# Controller.net
KiCad netlist of a schematic drawn in Altium Designer
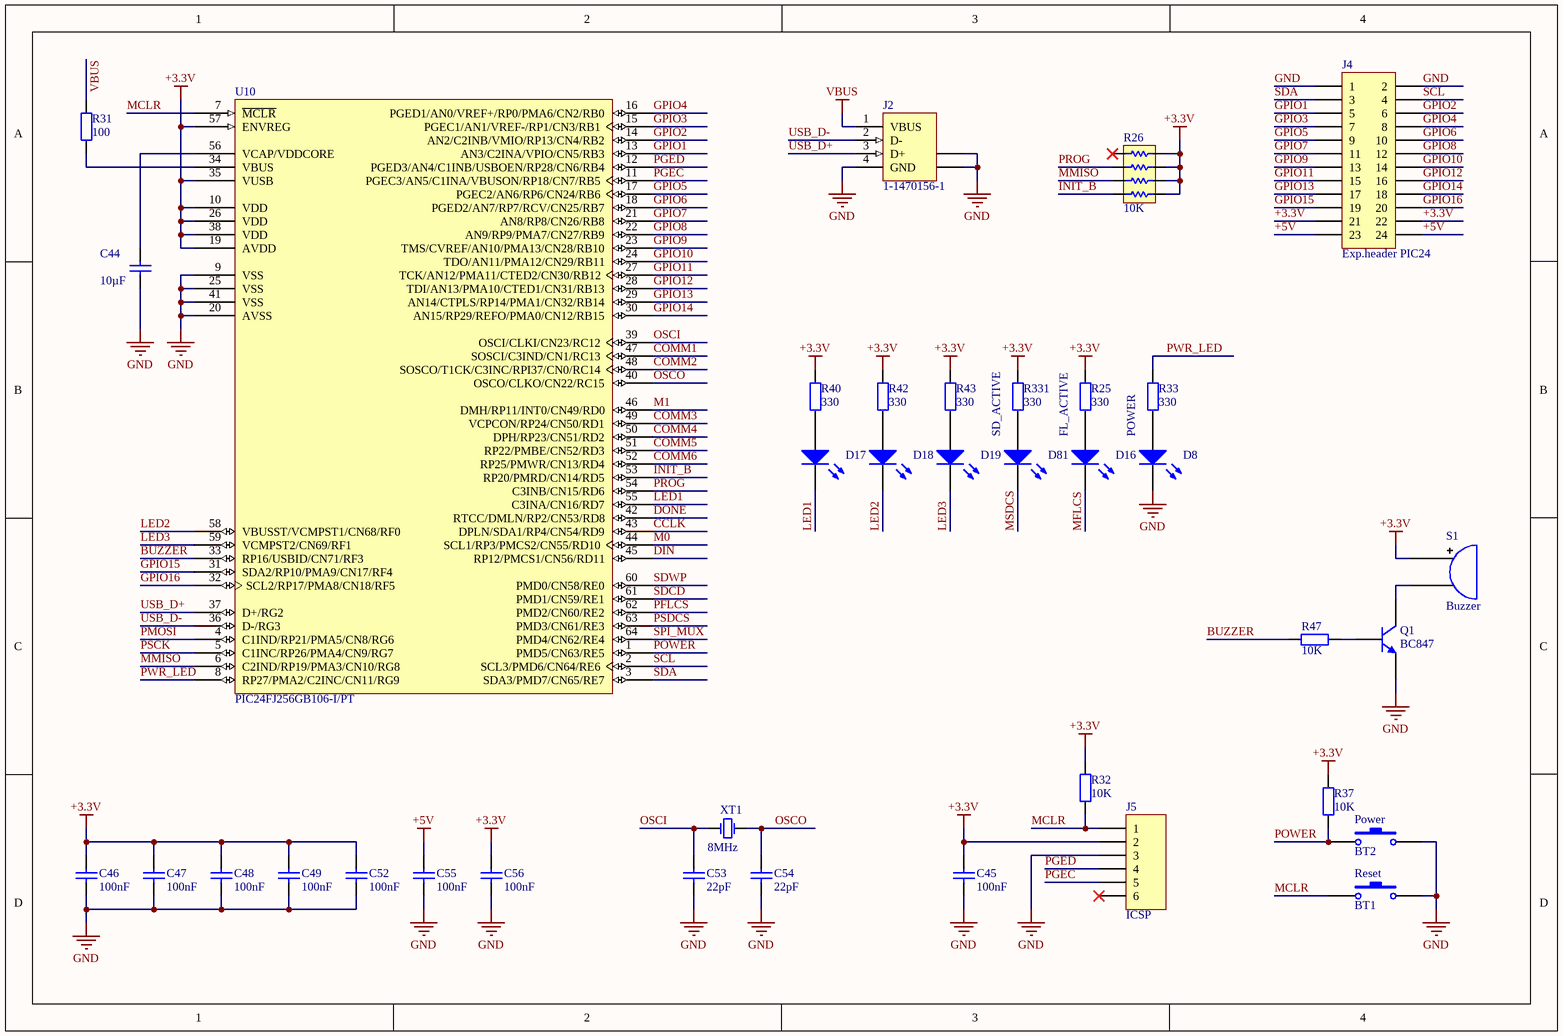
[diagram p0: Controller.SchDoc]

(export (version "E")
  (design (tool "Eeschema 10.0.6"))
  (components
    (comp (ref "C44")
      (value "10µF")
      (footprint "6-0805_n")
      (description "Capacitor")
      (fields (field (name "Comment") "Cap") (field (name "PUBLISHER") "Altium Limited"))
      (libsource (lib "Miscellaneous Devices") (part "Cap"))
    )
    (comp (ref "C45")
      (value "100nF")
      (footprint "6-0805_n")
      (description "Capacitor")
      (fields (field (name "Comment") "Cap") (field (name "PUBLISHER") "Altium Limited"))
      (libsource (lib "Miscellaneous Devices") (part "Cap"))
    )
    (comp (ref "C46")
      (value "100nF")
      (footprint "6-0805_n")
      (description "Capacitor")
      (fields (field (name "Comment") "Cap") (field (name "PUBLISHER") "Altium Limited"))
      (libsource (lib "Miscellaneous Devices") (part "Cap"))
    )
    (comp (ref "C47")
      (value "100nF")
      (footprint "6-0805_n")
      (description "Capacitor")
      (fields (field (name "Comment") "Cap") (field (name "PUBLISHER") "Altium Limited"))
      (libsource (lib "Miscellaneous Devices") (part "Cap"))
    )
    (comp (ref "C48")
      (value "100nF")
      (footprint "6-0805_n")
      (description "Capacitor")
      (fields (field (name "Comment") "Cap") (field (name "PUBLISHER") "Altium Limited"))
      (libsource (lib "Miscellaneous Devices") (part "Cap"))
    )
    (comp (ref "C49")
      (value "100nF")
      (footprint "6-0805_n")
      (description "Capacitor")
      (fields (field (name "Comment") "Cap") (field (name "PUBLISHER") "Altium Limited"))
      (libsource (lib "Miscellaneous Devices") (part "Cap"))
    )
    (comp (ref "C52")
      (value "100nF")
      (footprint "6-0805_n")
      (description "Capacitor")
      (fields (field (name "Comment") "Cap") (field (name "PUBLISHER") "Altium Limited"))
      (libsource (lib "Miscellaneous Devices") (part "Cap"))
    )
    (comp (ref "C53")
      (value "22pF")
      (footprint "6-0805_n")
      (description "Capacitor")
      (fields (field (name "Comment") "Cap") (field (name "PUBLISHER") "Altium Limited"))
      (libsource (lib "Miscellaneous Devices") (part "Cap"))
    )
    (comp (ref "C54")
      (value "22pF")
      (footprint "6-0805_n")
      (description "Capacitor")
      (fields (field (name "Comment") "Cap") (field (name "PUBLISHER") "Altium Limited"))
      (libsource (lib "Miscellaneous Devices") (part "Cap"))
    )
    (comp (ref "C55")
      (value "100nF")
      (footprint "6-0805_n")
      (description "Capacitor")
      (fields (field (name "Comment") "Cap") (field (name "PUBLISHER") "Altium Limited"))
      (libsource (lib "Miscellaneous Devices") (part "Cap"))
    )
    (comp (ref "C56")
      (value "100nF")
      (footprint "6-0805_n")
      (description "Capacitor")
      (fields (field (name "Comment") "Cap") (field (name "PUBLISHER") "Altium Limited"))
      (libsource (lib "Miscellaneous Devices") (part "Cap"))
    )
    (comp (ref "D8")
      (value "POWER")
      (footprint "HDR1X2")
      (description "Typical INFRARED GaAs LED")
      (fields (field (name "PUBLISHER") "Altium Limited"))
      (libsource (lib "Miscellaneous Devices") (part "LED0"))
    )
    (comp (ref "D16")
      (value "FL_ACTIVE")
      (footprint "HDR1X2")
      (description "Typical INFRARED GaAs LED")
      (fields (field (name "PUBLISHER") "Altium Limited"))
      (libsource (lib "Miscellaneous Devices") (part "LED0"))
    )
    (comp (ref "D17")
      (value "SD_ACTIVE")
      (footprint "6-0805_N")
      (description "Typical INFRARED GaAs LED")
      (fields (field (name "PUBLISHER") "Altium Limited"))
      (libsource (lib "Miscellaneous Devices") (part "LED0"))
    )
    (comp (ref "D18")
      (value "SD_ACTIVE")
      (footprint "6-0805_N")
      (description "Typical INFRARED GaAs LED")
      (fields (field (name "PUBLISHER") "Altium Limited"))
      (libsource (lib "Miscellaneous Devices") (part "LED0"))
    )
    (comp (ref "D19")
      (value "SD_ACTIVE")
      (footprint "6-0805_N")
      (description "Typical INFRARED GaAs LED")
      (fields (field (name "PUBLISHER") "Altium Limited"))
      (libsource (lib "Miscellaneous Devices") (part "LED0"))
    )
    (comp (ref "D81")
      (value "SD_ACTIVE")
      (footprint "HDR1X2")
      (description "Typical INFRARED GaAs LED")
      (fields (field (name "PUBLISHER") "Altium Limited"))
      (libsource (lib "Miscellaneous Devices") (part "LED0"))
    )
    (comp (ref "J2")
      (value "1-1470156-1")
      (footprint "440119")
      (description "USB 1.1, Right Angle, Thru-Hole, B Type, Receptacle, 4 Position, White")
      (fields (field (name "PUBLISHER") "Altium Limited"))
      (libsource (lib "AMP Serial Bus USB") (part "1-1470156-1"))
    )
    (comp (ref "J4")
      (value "Exp.header PIC24")
      (footprint "HDR2X12")
      (description "Header, 12-Pin, Dual row")
      (fields (field (name "PUBLISHER") "Altium Limited"))
      (libsource (lib "Miscellaneous Connectors") (part "Header 12X2"))
    )
    (comp (ref "J5")
      (value "ICSP")
      (footprint "HDR1X6")
      (description "Header, 6-Pin")
      (fields (field (name "PUBLISHER") "Altium Limited"))
      (libsource (lib "Miscellaneous Connectors") (part "Header 6"))
    )
    (comp (ref "Power")
      (value "BT2")
      (footprint "Push Button 6mm - Right Angle")
      (libsource (lib "Switches Buttons") (part "Push Button"))
    )
    (comp (ref "Q1")
      (value "BC847")
      (footprint "SOT23_N")
      (description "NPN 1 GHz Wideband Transistor")
      (fields (field (name "PUBLISHER") "Altium Limited"))
      (libsource (lib "Philips Discrete BJT - RF Transistor") (part "BF547"))
    )
    (comp (ref "R25")
      (value "330")
      (footprint "6-0805_N")
      (description "Resistor")
      (fields (field (name "Comment") "Res2") (field (name "PUBLISHER") "Altium Limited"))
      (libsource (lib "Miscellaneous Devices") (part "Res2"))
    )
    (comp (ref "R26")
      (value "10K")
      (footprint "SMD 4 Resisor Network")
      (libsource (lib "eon_lib") (part "SMD 4 Resistor Network"))
    )
    (comp (ref "R31")
      (value "100")
      (footprint "6-0805_N")
      (description "Resistor")
      (fields (field (name "Comment") "Res2") (field (name "PUBLISHER") "Altium Limited"))
      (libsource (lib "") (part "Res2_1"))
    )
    (comp (ref "R32")
      (value "10K")
      (footprint "6-0805_N")
      (description "Resistor")
      (fields (field (name "Comment") "Res2") (field (name "PUBLISHER") "Altium Limited"))
      (libsource (lib "Miscellaneous Devices") (part "Res2"))
    )
    (comp (ref "R33")
      (value "330")
      (footprint "6-0805_N")
      (description "Resistor")
      (fields (field (name "Comment") "Res2") (field (name "PUBLISHER") "Altium Limited"))
      (libsource (lib "Miscellaneous Devices") (part "Res2"))
    )
    (comp (ref "R37")
      (value "10K")
      (footprint "6-0805_N")
      (description "Resistor")
      (fields (field (name "Comment") "Res2") (field (name "PUBLISHER") "Altium Limited"))
      (libsource (lib "Miscellaneous Devices") (part "Res2"))
    )
    (comp (ref "R40")
      (value "330")
      (footprint "6-0805_N")
      (description "Resistor")
      (fields (field (name "Comment") "Res2") (field (name "PUBLISHER") "Altium Limited"))
      (libsource (lib "Miscellaneous Devices") (part "Res2"))
    )
    (comp (ref "R42")
      (value "330")
      (footprint "6-0805_N")
      (description "Resistor")
      (fields (field (name "Comment") "Res2") (field (name "PUBLISHER") "Altium Limited"))
      (libsource (lib "Miscellaneous Devices") (part "Res2"))
    )
    (comp (ref "R43")
      (value "330")
      (footprint "6-0805_N")
      (description "Resistor")
      (fields (field (name "Comment") "Res2") (field (name "PUBLISHER") "Altium Limited"))
      (libsource (lib "Miscellaneous Devices") (part "Res2"))
    )
    (comp (ref "R47")
      (value "10K")
      (footprint "RESC2012N")
      (description "Resistor")
      (fields (field (name "PUBLISHER") "Altium Limited"))
      (libsource (lib "eon_lib") (part "Resistor"))
    )
    (comp (ref "R331")
      (value "330")
      (footprint "6-0805_N")
      (description "Resistor")
      (fields (field (name "Comment") "Res2") (field (name "PUBLISHER") "Altium Limited"))
      (libsource (lib "Miscellaneous Devices") (part "Res2"))
    )
    (comp (ref "Reset")
      (value "BT1")
      (footprint "Push Button 6mm")
      (libsource (lib "Switches Buttons") (part "Push Button"))
    )
    (comp (ref "S1")
      (value "Buzzer")
      (footprint "Buzzer")
      (description "Magnetic Buzzer")
      (libsource (lib "eon_lib") (part "Buzzer CEM-1206S/WT-1201"))
    )
    (comp (ref "U10")
      (value "PIC24FJ256GB106-I/PT")
      (footprint "TQFP-PT64_N")
      (fields (field (name "PUBLISHER") "Altium Limited"))
      (libsource (lib "Microchip Microcontroller 16-Bit PIC24F") (part "PIC24FJ256GB106-I/PT"))
    )
    (comp (ref "XT1")
      (value "8MHz")
      (footprint "Quartz HC-49")
      (fields (field (name "Comment") "XTAL"))
      (libsource (lib "Passiv") (part "XTAL"))
    )
  )
  (nets
    (net (code "1") (name "+3.3V") (class "Default")
      (node (ref "C45") (pin "2") (pinfunction "2_2") (pintype "passive"))
      (node (ref "C46") (pin "1") (pinfunction "1_1") (pintype "passive"))
      (node (ref "C47") (pin "1") (pinfunction "1_1") (pintype "passive"))
      (node (ref "C48") (pin "1") (pinfunction "1_1") (pintype "passive"))
      (node (ref "C49") (pin "1") (pinfunction "1_1") (pintype "passive"))
      (node (ref "C52") (pin "1") (pinfunction "1_1") (pintype "passive"))
      (node (ref "C56") (pin "2") (pinfunction "2_2") (pintype "passive"))
      (node (ref "J4") (pin "21") (pinfunction "21_21") (pintype "passive"))
      (node (ref "J4") (pin "22") (pinfunction "22_22") (pintype "passive"))
      (node (ref "J5") (pin "2") (pinfunction "2_2") (pintype "passive"))
      (node (ref "R25") (pin "2") (pinfunction "2_2") (pintype "passive"))
      (node (ref "R26") (pin "2") (pinfunction "2_2") (pintype "passive"))
      (node (ref "R26") (pin "4") (pinfunction "4_4") (pintype "passive"))
      (node (ref "R26") (pin "6") (pinfunction "6_6") (pintype "passive"))
      (node (ref "R26") (pin "8") (pinfunction "8_8") (pintype "passive"))
      (node (ref "R32") (pin "2") (pinfunction "2_2") (pintype "passive"))
      (node (ref "R331") (pin "2") (pinfunction "2_2") (pintype "passive"))
      (node (ref "R37") (pin "2") (pinfunction "2_2") (pintype "passive"))
      (node (ref "R40") (pin "2") (pinfunction "2_2") (pintype "passive"))
      (node (ref "R42") (pin "2") (pinfunction "2_2") (pintype "passive"))
      (node (ref "R43") (pin "2") (pinfunction "2_2") (pintype "passive"))
      (node (ref "S1") (pin "1") (pinfunction "1_1") (pintype "passive"))
      (node (ref "U10") (pin "10") (pinfunction "VDD_10") (pintype "power_in"))
      (node (ref "U10") (pin "19") (pinfunction "AVDD_19") (pintype "power_in"))
      (node (ref "U10") (pin "26") (pinfunction "VDD_26") (pintype "power_in"))
      (node (ref "U10") (pin "35") (pinfunction "VUSB_35") (pintype "power_in"))
      (node (ref "U10") (pin "38") (pinfunction "VDD_38") (pintype "power_in"))
      (node (ref "U10") (pin "57") (pinfunction "ENVREG_57") (pintype "input"))
    )
    (net (code "2") (name "+5V") (class "Default")
      (node (ref "C55") (pin "2") (pinfunction "2_2") (pintype "passive"))
      (node (ref "J4") (pin "23") (pinfunction "23_23") (pintype "passive"))
      (node (ref "J4") (pin "24") (pinfunction "24_24") (pintype "passive"))
    )
    (net (code "3") (name "/BUZZER") (class "Default")
      (node (ref "R47") (pin "1") (pinfunction "1_1") (pintype "passive"))
      (node (ref "U10") (pin "33") (pinfunction "RP16/USBID/CN71/RF3_33") (pintype "bidirectional"))
    )
    (net (code "4") (name "/CCLK") (class "Default")
      (node (ref "U10") (pin "43") (pinfunction "DPLN/SDA1/RP4/CN54/RD9_43") (pintype "bidirectional"))
    )
    (net (code "5") (name "/COMM1") (class "Default")
      (node (ref "U10") (pin "47") (pinfunction "SOSCI/C3IND/CN1/RC13_47") (pintype "bidirectional"))
    )
    (net (code "6") (name "/COMM2") (class "Default")
      (node (ref "U10") (pin "48") (pinfunction "SOSCO/T1CK/C3INC/RPI37/CN0/RC14_48") (pintype "bidirectional"))
    )
    (net (code "7") (name "/COMM3") (class "Default")
      (node (ref "U10") (pin "49") (pinfunction "VCPCON/RP24/CN50/RD1_49") (pintype "bidirectional"))
    )
    (net (code "8") (name "/COMM4") (class "Default")
      (node (ref "U10") (pin "50") (pinfunction "DPH/RP23/CN51/RD2_50") (pintype "bidirectional"))
    )
    (net (code "9") (name "/COMM5") (class "Default")
      (node (ref "U10") (pin "51") (pinfunction "RP22/PMBE/CN52/RD3_51") (pintype "bidirectional"))
    )
    (net (code "10") (name "/COMM6") (class "Default")
      (node (ref "U10") (pin "52") (pinfunction "RP25/PMWR/CN13/RD4_52") (pintype "bidirectional"))
    )
    (net (code "11") (name "/DIN") (class "Default")
      (node (ref "U10") (pin "45") (pinfunction "RP12/PMCS1/CN56/RD11_45") (pintype "bidirectional"))
    )
    (net (code "12") (name "/DONE") (class "Default")
      (node (ref "U10") (pin "42") (pinfunction "RTCC/DMLN/RP2/CN53/RD8_42") (pintype "bidirectional"))
    )
    (net (code "13") (name "/GPIO1") (class "Default")
      (node (ref "J4") (pin "5") (pinfunction "5_5") (pintype "passive"))
      (node (ref "U10") (pin "13") (pinfunction "AN3/C2INA/VPIO/CN5/RB3_13") (pintype "bidirectional"))
    )
    (net (code "14") (name "/GPIO2") (class "Default")
      (node (ref "J4") (pin "6") (pinfunction "6_6") (pintype "passive"))
      (node (ref "U10") (pin "14") (pinfunction "AN2/C2INB/VMIO/RP13/CN4/RB2_14") (pintype "bidirectional"))
    )
    (net (code "15") (name "/GPIO3") (class "Default")
      (node (ref "J4") (pin "7") (pinfunction "7_7") (pintype "passive"))
      (node (ref "U10") (pin "15") (pinfunction "PGEC1/AN1/VREF-/RP1/CN3/RB1_15") (pintype "bidirectional"))
    )
    (net (code "16") (name "/GPIO4") (class "Default")
      (node (ref "J4") (pin "8") (pinfunction "8_8") (pintype "passive"))
      (node (ref "U10") (pin "16") (pinfunction "PGED1/AN0/VREF+/RP0/PMA6/CN2/RB0_16") (pintype "bidirectional"))
    )
    (net (code "17") (name "/GPIO5") (class "Default")
      (node (ref "J4") (pin "9") (pinfunction "9_9") (pintype "passive"))
      (node (ref "U10") (pin "17") (pinfunction "PGEC2/AN6/RP6/CN24/RB6_17") (pintype "bidirectional"))
    )
    (net (code "18") (name "/GPIO6") (class "Default")
      (node (ref "J4") (pin "10") (pinfunction "10_10") (pintype "passive"))
      (node (ref "U10") (pin "18") (pinfunction "PGED2/AN7/RP7/RCV/CN25/RB7_18") (pintype "bidirectional"))
    )
    (net (code "19") (name "/GPIO7") (class "Default")
      (node (ref "J4") (pin "11") (pinfunction "11_11") (pintype "passive"))
      (node (ref "U10") (pin "21") (pinfunction "AN8/RP8/CN26/RB8_21") (pintype "bidirectional"))
    )
    (net (code "20") (name "/GPIO8") (class "Default")
      (node (ref "J4") (pin "12") (pinfunction "12_12") (pintype "passive"))
      (node (ref "U10") (pin "22") (pinfunction "AN9/RP9/PMA7/CN27/RB9_22") (pintype "bidirectional"))
    )
    (net (code "21") (name "/GPIO9") (class "Default")
      (node (ref "J4") (pin "13") (pinfunction "13_13") (pintype "passive"))
      (node (ref "U10") (pin "23") (pinfunction "TMS/CVREF/AN10/PMA13/CN28/RB10_23") (pintype "bidirectional"))
    )
    (net (code "22") (name "/GPIO10") (class "Default")
      (node (ref "J4") (pin "14") (pinfunction "14_14") (pintype "passive"))
      (node (ref "U10") (pin "24") (pinfunction "TDO/AN11/PMA12/CN29/RB11_24") (pintype "bidirectional"))
    )
    (net (code "23") (name "/GPIO11") (class "Default")
      (node (ref "J4") (pin "15") (pinfunction "15_15") (pintype "passive"))
      (node (ref "U10") (pin "27") (pinfunction "TCK/AN12/PMA11/CTED2/CN30/RB12_27") (pintype "bidirectional"))
    )
    (net (code "24") (name "/GPIO12") (class "Default")
      (node (ref "J4") (pin "16") (pinfunction "16_16") (pintype "passive"))
      (node (ref "U10") (pin "28") (pinfunction "TDI/AN13/PMA10/CTED1/CN31/RB13_28") (pintype "bidirectional"))
    )
    (net (code "25") (name "/GPIO13") (class "Default")
      (node (ref "J4") (pin "17") (pinfunction "17_17") (pintype "passive"))
      (node (ref "U10") (pin "29") (pinfunction "AN14/CTPLS/RP14/PMA1/CN32/RB14_29") (pintype "bidirectional"))
    )
    (net (code "26") (name "/GPIO14") (class "Default")
      (node (ref "J4") (pin "18") (pinfunction "18_18") (pintype "passive"))
      (node (ref "U10") (pin "30") (pinfunction "AN15/RP29/REFO/PMA0/CN12/RB15_30") (pintype "bidirectional"))
    )
    (net (code "27") (name "/GPIO15") (class "Default")
      (node (ref "J4") (pin "19") (pinfunction "19_19") (pintype "passive"))
      (node (ref "U10") (pin "31") (pinfunction "SDA2/RP10/PMA9/CN17/RF4_31") (pintype "bidirectional"))
    )
    (net (code "28") (name "/GPIO16") (class "Default")
      (node (ref "J4") (pin "20") (pinfunction "20_20") (pintype "passive"))
      (node (ref "U10") (pin "32") (pinfunction "SCL2/RP17/PMA8/CN18/RF5_32") (pintype "bidirectional"))
    )
    (net (code "29") (name "/INIT_B") (class "Default")
      (node (ref "R26") (pin "7") (pinfunction "7_7") (pintype "passive"))
      (node (ref "U10") (pin "53") (pinfunction "RP20/PMRD/CN14/RD5_53") (pintype "bidirectional"))
    )
    (net (code "30") (name "/LED1") (class "Default")
      (node (ref "D17") (pin "2") (pinfunction "K_2") (pintype "passive"))
      (node (ref "U10") (pin "55") (pinfunction "C3INA/CN16/RD7_55") (pintype "bidirectional"))
    )
    (net (code "31") (name "/LED2") (class "Default")
      (node (ref "D18") (pin "2") (pinfunction "K_2") (pintype "passive"))
      (node (ref "U10") (pin "58") (pinfunction "VBUSST/VCMPST1/CN68/RF0_58") (pintype "bidirectional"))
    )
    (net (code "32") (name "/LED3") (class "Default")
      (node (ref "D19") (pin "2") (pinfunction "K_2") (pintype "passive"))
      (node (ref "U10") (pin "59") (pinfunction "VCMPST2/CN69/RF1_59") (pintype "bidirectional"))
    )
    (net (code "33") (name "/M0") (class "Default")
      (node (ref "U10") (pin "44") (pinfunction "SCL1/RP3/PMCS2/CN55/RD10_44") (pintype "bidirectional"))
    )
    (net (code "34") (name "/M1") (class "Default")
      (node (ref "U10") (pin "46") (pinfunction "DMH/RP11/INT0/CN49/RD0_46") (pintype "bidirectional"))
    )
    (net (code "35") (name "/MCLR") (class "Default")
      (node (ref "J5") (pin "1") (pinfunction "1_1") (pintype "passive"))
      (node (ref "R32") (pin "1") (pinfunction "1_1") (pintype "passive"))
      (node (ref "Reset") (pin "1") (pinfunction "1_1") (pintype "passive"))
      (node (ref "U10") (pin "7") (pinfunction "~{MCLR}_7") (pintype "input"))
    )
    (net (code "36") (name "/MFLCS") (class "Default")
      (node (ref "D16") (pin "2") (pinfunction "K_2") (pintype "passive"))
    )
    (net (code "37") (name "/MMISO") (class "Default")
      (node (ref "R26") (pin "5") (pinfunction "5_5") (pintype "passive"))
      (node (ref "U10") (pin "6") (pinfunction "C2IND/RP19/PMA3/CN10/RG8_6") (pintype "bidirectional"))
    )
    (net (code "38") (name "/MSDCS") (class "Default")
      (node (ref "D81") (pin "2") (pinfunction "K_2") (pintype "passive"))
    )
    (net (code "39") (name "/OSCI") (class "Default")
      (node (ref "C53") (pin "2") (pinfunction "2_2") (pintype "passive"))
      (node (ref "U10") (pin "39") (pinfunction "OSCI/CLKI/CN23/RC12_39") (pintype "bidirectional"))
      (node (ref "XT1") (pin "2") (pinfunction "OSC2_2") (pintype "passive"))
    )
    (net (code "40") (name "/OSCO") (class "Default")
      (node (ref "C54") (pin "2") (pinfunction "2_2") (pintype "passive"))
      (node (ref "U10") (pin "40") (pinfunction "OSCO/CLKO/CN22/RC15_40") (pintype "bidirectional"))
      (node (ref "XT1") (pin "1") (pinfunction "OSC1_1") (pintype "passive"))
    )
    (net (code "41") (name "/PFLCS") (class "Default")
      (node (ref "U10") (pin "62") (pinfunction "PMD2/CN60/RE2_62") (pintype "bidirectional"))
    )
    (net (code "42") (name "/PGEC") (class "Default")
      (node (ref "J5") (pin "5") (pinfunction "5_5") (pintype "passive"))
      (node (ref "U10") (pin "11") (pinfunction "PGEC3/AN5/C1INA/VBUSON/RP18/CN7/RB5_11") (pintype "bidirectional"))
    )
    (net (code "43") (name "/PGED") (class "Default")
      (node (ref "J5") (pin "4") (pinfunction "4_4") (pintype "passive"))
      (node (ref "U10") (pin "12") (pinfunction "PGED3/AN4/C1INB/USBOEN/RP28/CN6/RB4_12") (pintype "bidirectional"))
    )
    (net (code "44") (name "/PMOSI") (class "Default")
      (node (ref "U10") (pin "4") (pinfunction "C1IND/RP21/PMA5/CN8/RG6_4") (pintype "bidirectional"))
    )
    (net (code "45") (name "/POWER") (class "Default")
      (node (ref "Power") (pin "2") (pinfunction "2_2") (pintype "passive"))
      (node (ref "R37") (pin "1") (pinfunction "1_1") (pintype "passive"))
      (node (ref "U10") (pin "1") (pinfunction "PMD5/CN63/RE5_1") (pintype "bidirectional"))
    )
    (net (code "46") (name "/PROG") (class "Default")
      (node (ref "R26") (pin "3") (pinfunction "3_3") (pintype "passive"))
      (node (ref "U10") (pin "54") (pinfunction "C3INB/CN15/RD6_54") (pintype "bidirectional"))
    )
    (net (code "47") (name "/PSCK") (class "Default")
      (node (ref "U10") (pin "5") (pinfunction "C1INC/RP26/PMA4/CN9/RG7_5") (pintype "bidirectional"))
    )
    (net (code "48") (name "/PSDCS") (class "Default")
      (node (ref "U10") (pin "63") (pinfunction "PMD3/CN61/RE3_63") (pintype "bidirectional"))
    )
    (net (code "49") (name "/PWR_LED") (class "Default")
      (node (ref "R33") (pin "2") (pinfunction "2_2") (pintype "passive"))
      (node (ref "U10") (pin "8") (pinfunction "RP27/PMA2/C2INC/CN11/RG9_8") (pintype "bidirectional"))
    )
    (net (code "50") (name "/SCL") (class "Default")
      (node (ref "J4") (pin "4") (pinfunction "4_4") (pintype "passive"))
      (node (ref "U10") (pin "2") (pinfunction "SCL3/PMD6/CN64/RE6_2") (pintype "bidirectional"))
    )
    (net (code "51") (name "/SDA") (class "Default")
      (node (ref "J4") (pin "3") (pinfunction "3_3") (pintype "passive"))
      (node (ref "U10") (pin "3") (pinfunction "SDA3/PMD7/CN65/RE7_3") (pintype "bidirectional"))
    )
    (net (code "52") (name "/SDCD") (class "Default")
      (node (ref "U10") (pin "61") (pinfunction "PMD1/CN59/RE1_61") (pintype "bidirectional"))
    )
    (net (code "53") (name "/SDWP") (class "Default")
      (node (ref "U10") (pin "60") (pinfunction "PMD0/CN58/RE0_60") (pintype "bidirectional"))
    )
    (net (code "54") (name "/SPI_MUX") (class "Default")
      (node (ref "U10") (pin "64") (pinfunction "PMD4/CN62/RE4_64") (pintype "bidirectional"))
    )
    (net (code "55") (name "/USB_D+") (class "Default")
      (node (ref "J2") (pin "3") (pinfunction "D+_3") (pintype "input"))
      (node (ref "U10") (pin "37") (pinfunction "D+/RG2_37") (pintype "bidirectional"))
    )
    (net (code "56") (name "/USB_D-") (class "Default")
      (node (ref "J2") (pin "2") (pinfunction "D-_2") (pintype "input"))
      (node (ref "U10") (pin "36") (pinfunction "D-/RG3_36") (pintype "bidirectional"))
    )
    (net (code "57") (name "GND") (class "Default")
      (node (ref "C44") (pin "1") (pinfunction "1_1") (pintype "passive"))
      (node (ref "C45") (pin "1") (pinfunction "1_1") (pintype "passive"))
      (node (ref "C46") (pin "2") (pinfunction "2_2") (pintype "passive"))
      (node (ref "C47") (pin "2") (pinfunction "2_2") (pintype "passive"))
      (node (ref "C48") (pin "2") (pinfunction "2_2") (pintype "passive"))
      (node (ref "C49") (pin "2") (pinfunction "2_2") (pintype "passive"))
      (node (ref "C52") (pin "2") (pinfunction "2_2") (pintype "passive"))
      (node (ref "C53") (pin "1") (pinfunction "1_1") (pintype "passive"))
      (node (ref "C54") (pin "1") (pinfunction "1_1") (pintype "passive"))
      (node (ref "C55") (pin "1") (pinfunction "1_1") (pintype "passive"))
      (node (ref "C56") (pin "1") (pinfunction "1_1") (pintype "passive"))
      (node (ref "D8") (pin "2") (pinfunction "K_2") (pintype "passive"))
      (node (ref "J2") (pin "4") (pinfunction "GND_4") (pintype "power_in"))
      (node (ref "J2") (pin "5") (pinfunction "SHLD_5") (pintype "passive"))
      (node (ref "J2") (pin "6") (pinfunction "SHLD_6") (pintype "passive"))
      (node (ref "J4") (pin "1") (pinfunction "1_1") (pintype "passive"))
      (node (ref "J4") (pin "2") (pinfunction "2_2") (pintype "passive"))
      (node (ref "J5") (pin "3") (pinfunction "3_3") (pintype "passive"))
      (node (ref "Power") (pin "1") (pinfunction "1_1") (pintype "passive"))
      (node (ref "Q1") (pin "2") (pinfunction "E_2") (pintype "passive"))
      (node (ref "Reset") (pin "2") (pinfunction "2_2") (pintype "passive"))
      (node (ref "U10") (pin "20") (pinfunction "AVSS_20") (pintype "power_in"))
      (node (ref "U10") (pin "25") (pinfunction "VSS_25") (pintype "power_in"))
      (node (ref "U10") (pin "41") (pinfunction "VSS_41") (pintype "power_in"))
      (node (ref "U10") (pin "9") (pinfunction "VSS_9") (pintype "power_in"))
    )
    (net (code "58") (name "Net-(D8-A)") (class "Default")
      (node (ref "D8") (pin "1") (pinfunction "A_1") (pintype "passive"))
      (node (ref "R33") (pin "1") (pinfunction "1_1") (pintype "passive"))
    )
    (net (code "59") (name "Net-(D16-A)") (class "Default")
      (node (ref "D16") (pin "1") (pinfunction "A_1") (pintype "passive"))
      (node (ref "R25") (pin "1") (pinfunction "1_1") (pintype "passive"))
    )
    (net (code "60") (name "Net-(D17-A)") (class "Default")
      (node (ref "D17") (pin "1") (pinfunction "A_1") (pintype "passive"))
      (node (ref "R40") (pin "1") (pinfunction "1_1") (pintype "passive"))
    )
    (net (code "61") (name "Net-(D18-A)") (class "Default")
      (node (ref "D18") (pin "1") (pinfunction "A_1") (pintype "passive"))
      (node (ref "R42") (pin "1") (pinfunction "1_1") (pintype "passive"))
    )
    (net (code "62") (name "Net-(D19-A)") (class "Default")
      (node (ref "D19") (pin "1") (pinfunction "A_1") (pintype "passive"))
      (node (ref "R43") (pin "1") (pinfunction "1_1") (pintype "passive"))
    )
    (net (code "63") (name "Net-(D81-A)") (class "Default")
      (node (ref "D81") (pin "1") (pinfunction "A_1") (pintype "passive"))
      (node (ref "R331") (pin "1") (pinfunction "1_1") (pintype "passive"))
    )
    (net (code "64") (name "Net-(Q1-B)") (class "Default")
      (node (ref "Q1") (pin "1") (pinfunction "B_1") (pintype "passive"))
      (node (ref "R47") (pin "2") (pinfunction "2_2") (pintype "passive"))
    )
    (net (code "65") (name "Net-(Q1-C)") (class "Default")
      (node (ref "Q1") (pin "3") (pinfunction "C_3") (pintype "passive"))
      (node (ref "S1") (pin "2") (pinfunction "2_2") (pintype "passive"))
    )
    (net (code "66") (name "Net-(U10-VBUS)") (class "Default")
      (node (ref "R31") (pin "2") (pinfunction "2_2") (pintype "passive"))
      (node (ref "U10") (pin "34") (pinfunction "VBUS_34") (pintype "power_in"))
    )
    (net (code "67") (name "Net-(U10-VCAP{slash}VDDCORE)") (class "Default")
      (node (ref "C44") (pin "2") (pinfunction "2_2") (pintype "passive"))
      (node (ref "U10") (pin "56") (pinfunction "VCAP/VDDCORE_56") (pintype "power_in"))
    )
    (net (code "68") (name "VBUS") (class "Default")
      (node (ref "J2") (pin "1") (pinfunction "VBUS_1") (pintype "power_in"))
      (node (ref "R31") (pin "1") (pinfunction "1_1") (pintype "passive"))
    )
    (net (code "69") (name "unconnected-(J5-Pad6)") (class "Default")
      (node (ref "J5") (pin "6") (pinfunction "6_6") (pintype "passive+no_connect"))
    )
    (net (code "70") (name "unconnected-(R26-Pad1)") (class "Default")
      (node (ref "R26") (pin "1") (pinfunction "1_1") (pintype "passive+no_connect"))
    )
  )
)
